# decision.net
KiCad netlist of a schematic drawn in EAGLE
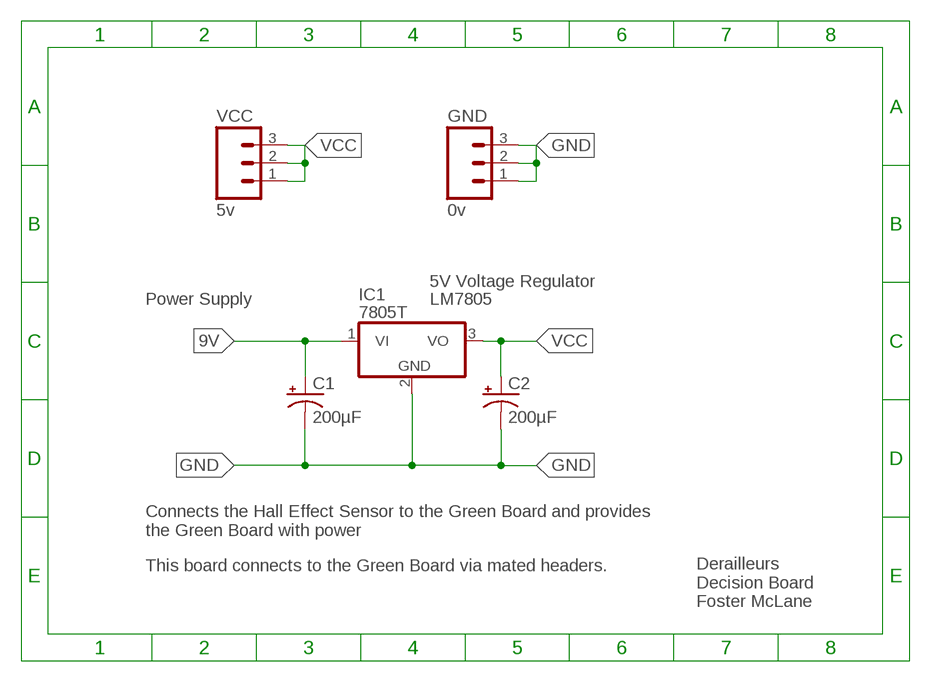
[diagram p0: schematic, sheet 1]

(export (version "E")
  (design (tool "Eeschema 10.0.6"))
  (components
    (comp (ref "C1")
      (value "200µF")
      (footprint "eagle-import:CPOL-RADIAL-100UF-25V")
      (libsource (lib "eagle-import") (part "CAP_POLPTH1"))
    )
    (comp (ref "C2")
      (value "200µF")
      (footprint "eagle-import:CPOL-RADIAL-100UF-25V")
      (libsource (lib "eagle-import") (part "CAP_POLPTH1"))
    )
    (comp (ref "GND")
      (value "0v")
      (footprint "eagle-import:1X03")
      (libsource (lib "eagle-import") (part "M03PTH"))
    )
    (comp (ref "IC1")
      (value "7805T")
      (footprint "eagle-import:TO220H")
      (libsource (lib "eagle-import") (part "78T05"))
    )
    (comp (ref "VCC")
      (value "5v")
      (footprint "eagle-import:1X03")
      (libsource (lib "eagle-import") (part "M03PTH"))
    )
  )
  (nets
    (net (code "1") (name "9V") (class "Default")
      (node (ref "C1") (pin "1") (pinfunction "+_1") (pintype "passive"))
      (node (ref "IC1") (pin "1") (pinfunction "VI_1") (pintype "input"))
    )
    (net (code "2") (name "GND") (class "Default")
      (node (ref "C1") (pin "2") (pinfunction "-_2") (pintype "passive"))
      (node (ref "C2") (pin "2") (pinfunction "-_2") (pintype "passive"))
      (node (ref "GND") (pin "1") (pinfunction "1_1") (pintype "passive"))
      (node (ref "GND") (pin "2") (pinfunction "2_2") (pintype "passive"))
      (node (ref "GND") (pin "3") (pinfunction "3_3") (pintype "passive"))
      (node (ref "IC1") (pin "2") (pinfunction "GND_2") (pintype "passive"))
    )
    (net (code "3") (name "VCC") (class "Default")
      (node (ref "C2") (pin "1") (pinfunction "+_1") (pintype "passive"))
      (node (ref "IC1") (pin "3") (pinfunction "VO_3") (pintype "passive"))
      (node (ref "VCC") (pin "1") (pinfunction "1_1") (pintype "passive"))
      (node (ref "VCC") (pin "2") (pinfunction "2_2") (pintype "passive"))
      (node (ref "VCC") (pin "3") (pinfunction "3_3") (pintype "passive"))
    )
  )
)
